# PulseOxi.net
KiCad netlist of a schematic drawn in EAGLE
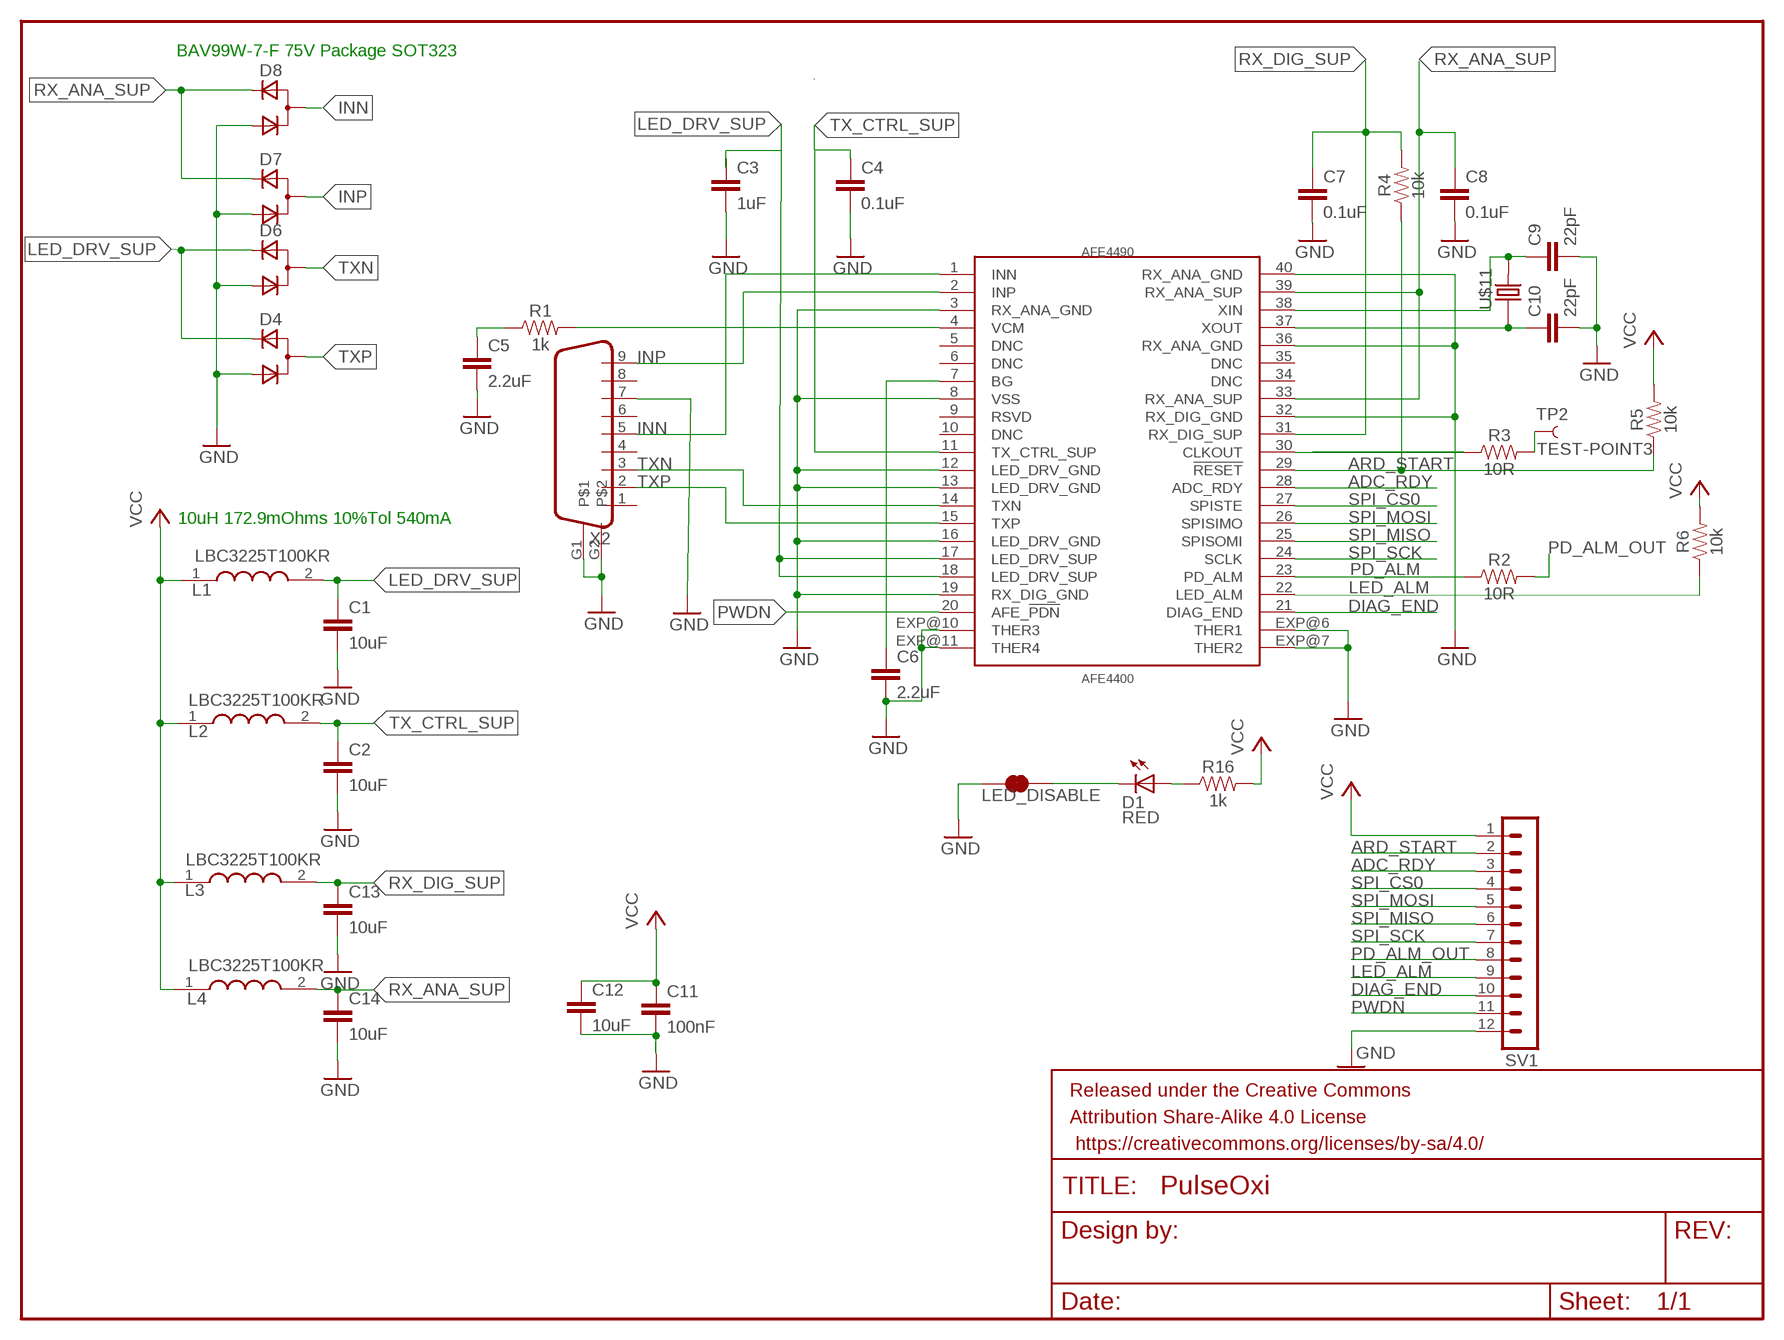
[diagram p0: schematic, sheet 1]

(export (version "E")
  (design (tool "Eeschema 10.0.6"))
  (components
    (comp (ref "AFE4490")
      (value "AFE4400")
      (footprint "eagle-import:QFN-40")
      (libsource (lib "eagle-import") (part "AFE4400"))
    )
    (comp (ref "C1")
      (value "10uF")
      (footprint "eagle-import:0603")
      (libsource (lib "eagle-import") (part "27PF-0603-50V-5%"))
    )
    (comp (ref "C2")
      (value "10uF")
      (footprint "eagle-import:0603")
      (libsource (lib "eagle-import") (part "27PF-0603-50V-5%"))
    )
    (comp (ref "C3")
      (value "1uF")
      (footprint "eagle-import:0603")
      (libsource (lib "eagle-import") (part "27PF-0603-50V-5%"))
    )
    (comp (ref "C4")
      (value "0.1uF")
      (footprint "eagle-import:0603")
      (libsource (lib "eagle-import") (part "27PF-0603-50V-5%"))
    )
    (comp (ref "C5")
      (value "2.2uF")
      (footprint "eagle-import:0603")
      (libsource (lib "eagle-import") (part "27PF-0603-50V-5%"))
    )
    (comp (ref "C6")
      (value "2.2uF")
      (footprint "eagle-import:0603")
      (libsource (lib "eagle-import") (part "27PF-0603-50V-5%"))
    )
    (comp (ref "C7")
      (value "0.1uF")
      (footprint "eagle-import:0603")
      (libsource (lib "eagle-import") (part "27PF-0603-50V-5%"))
    )
    (comp (ref "C8")
      (value "0.1uF")
      (footprint "eagle-import:0603")
      (libsource (lib "eagle-import") (part "27PF-0603-50V-5%"))
    )
    (comp (ref "C9")
      (value "22pF")
      (footprint "eagle-import:0603")
      (libsource (lib "eagle-import") (part "27PF-0603-50V-5%"))
    )
    (comp (ref "C10")
      (value "22pF")
      (footprint "eagle-import:0603")
      (libsource (lib "eagle-import") (part "27PF-0603-50V-5%"))
    )
    (comp (ref "C11")
      (value "100nF")
      (footprint "eagle-import:0603")
      (libsource (lib "eagle-import") (part "27PF-0603-50V-5%"))
    )
    (comp (ref "C12")
      (value "10uF")
      (footprint "eagle-import:0603")
      (libsource (lib "eagle-import") (part "27PF-0603-50V-5%"))
    )
    (comp (ref "C13")
      (value "10uF")
      (footprint "eagle-import:0603")
      (libsource (lib "eagle-import") (part "27PF-0603-50V-5%"))
    )
    (comp (ref "C14")
      (value "10uF")
      (footprint "eagle-import:0603")
      (libsource (lib "eagle-import") (part "27PF-0603-50V-5%"))
    )
    (comp (ref "D1")
      (value "RED")
      (footprint "eagle-import:LED-0603")
      (libsource (lib "eagle-import") (part "LED-RED0603"))
    )
    (comp (ref "D4")
      (value "D_ACACSOT323")
      (footprint "eagle-import:SOT323")
      (libsource (lib "eagle-import") (part "D_ACACSOT323"))
    )
    (comp (ref "D6")
      (value "D_ACACSOT323")
      (footprint "eagle-import:SOT323")
      (libsource (lib "eagle-import") (part "D_ACACSOT323"))
    )
    (comp (ref "D7")
      (value "D_ACACSOT323")
      (footprint "eagle-import:SOT323")
      (libsource (lib "eagle-import") (part "D_ACACSOT323"))
    )
    (comp (ref "D8")
      (value "D_ACACSOT323")
      (footprint "eagle-import:SOT323")
      (libsource (lib "eagle-import") (part "D_ACACSOT323"))
    )
    (comp (ref "FRAME1")
      (value "FRAME-LETTERNO_PACKAGE")
      (footprint "eagle-import:DUMMY")
      (fields (field (name "DESIGNER") "Nobody"))
      (libsource (lib "eagle-import") (part "FRAME-LETTERNO_PACKAGE"))
    )
    (comp (ref "L1")
      (value "LBC3225T100KR")
      (footprint "eagle-import:INDC3225X270N")
      (fields (field (name "MOUSER_PART_NUMBER") "963-LBC3225T100KR"))
      (libsource (lib "eagle-import") (part "LBC3225T100KR"))
    )
    (comp (ref "L2")
      (value "LBC3225T100KR")
      (footprint "eagle-import:INDC3225X270N")
      (fields (field (name "MOUSER_PART_NUMBER") "963-LBC3225T100KR"))
      (libsource (lib "eagle-import") (part "LBC3225T100KR"))
    )
    (comp (ref "L3")
      (value "LBC3225T100KR")
      (footprint "eagle-import:INDC3225X270N")
      (fields (field (name "MOUSER_PART_NUMBER") "963-LBC3225T100KR"))
      (libsource (lib "eagle-import") (part "LBC3225T100KR"))
    )
    (comp (ref "L4")
      (value "LBC3225T100KR")
      (footprint "eagle-import:INDC3225X270N")
      (fields (field (name "MOUSER_PART_NUMBER") "963-LBC3225T100KR"))
      (libsource (lib "eagle-import") (part "LBC3225T100KR"))
    )
    (comp (ref "LED_DISABLE")
      (value "JUMPER-SMT_2_NC_TRACE_SILK")
      (footprint "eagle-import:SMT-JUMPER_2_NC_TRACE_SILK")
      (libsource (lib "eagle-import") (part "JUMPER-SMT_2_NC_TRACE_SILK"))
    )
    (comp (ref "R1")
      (value "1k")
      (footprint "eagle-import:0603")
      (libsource (lib "eagle-import") (part "1KOHM-0603-1/10W-1%"))
    )
    (comp (ref "R2")
      (value "10R")
      (footprint "eagle-import:0603")
      (libsource (lib "eagle-import") (part "1.8MOHM"))
    )
    (comp (ref "R3")
      (value "10R")
      (footprint "eagle-import:0603")
      (libsource (lib "eagle-import") (part "1.8MOHM"))
    )
    (comp (ref "R4")
      (value "10k")
      (footprint "eagle-import:0603")
      (libsource (lib "eagle-import") (part "1.8MOHM"))
    )
    (comp (ref "R5")
      (value "10k")
      (footprint "eagle-import:0603")
      (libsource (lib "eagle-import") (part "1.8MOHM"))
    )
    (comp (ref "R6")
      (value "10k")
      (footprint "eagle-import:0603")
      (libsource (lib "eagle-import") (part "1.8MOHM"))
    )
    (comp (ref "R16")
      (value "1k")
      (footprint "eagle-import:0603")
      (libsource (lib "eagle-import") (part "1KOHM-0603-1/10W-1%"))
    )
    (comp (ref "SV1")
      (value "MA12-1")
      (footprint "eagle-import:MA12-1")
      (libsource (lib "eagle-import") (part "MA12-1"))
    )
    (comp (ref "TP2")
      (value "TEST-POINT3")
      (footprint "eagle-import:PAD.03X.03")
      (libsource (lib "eagle-import") (part "TEST-POINT3"))
    )
    (comp (ref "U$11")
      (value "ABM3")
      (footprint "eagle-import:ABM3")
      (libsource (lib "eagle-import") (part "ABM3"))
    )
    (comp (ref "X2")
      (value "DB9")
      (footprint "eagle-import:DB9")
      (libsource (lib "eagle-import") (part "DB9"))
    )
  )
  (nets
    (net (code "1") (name "/ADC_RDY") (class "Default")
      (node (ref "AFE4490") (pin "28") (pinfunction "ADC_RDY_28") (pintype "bidirectional"))
      (node (ref "SV1") (pin "3") (pinfunction "3_3") (pintype "passive"))
    )
    (net (code "2") (name "/ARD_START") (class "Default")
      (node (ref "AFE4490") (pin "29") (pinfunction "~{RESET}_29") (pintype "bidirectional"))
      (node (ref "R4") (pin "1") (pinfunction "1_1") (pintype "passive"))
      (node (ref "R5") (pin "1") (pinfunction "1_1") (pintype "passive"))
      (node (ref "SV1") (pin "2") (pinfunction "2_2") (pintype "passive"))
    )
    (net (code "3") (name "/DIAG_END") (class "Default")
      (node (ref "AFE4490") (pin "21") (pinfunction "DIAG_END_21") (pintype "bidirectional"))
      (node (ref "SV1") (pin "10") (pinfunction "10_10") (pintype "passive"))
    )
    (net (code "4") (name "/LED_ALM") (class "Default")
      (node (ref "AFE4490") (pin "22") (pinfunction "LED_ALM_22") (pintype "bidirectional"))
      (node (ref "R6") (pin "1") (pinfunction "1_1") (pintype "passive"))
      (node (ref "SV1") (pin "9") (pinfunction "9_9") (pintype "passive"))
    )
    (net (code "5") (name "/PD_ALM") (class "Default")
      (node (ref "AFE4490") (pin "23") (pinfunction "PD_ALM_23") (pintype "bidirectional"))
      (node (ref "R2") (pin "1") (pinfunction "1_1") (pintype "passive"))
    )
    (net (code "6") (name "/PD_ALM_OUT") (class "Default")
      (node (ref "R2") (pin "2") (pinfunction "2_2") (pintype "passive"))
      (node (ref "SV1") (pin "8") (pinfunction "8_8") (pintype "passive"))
    )
    (net (code "7") (name "/SPI_CS0") (class "Default")
      (node (ref "AFE4490") (pin "27") (pinfunction "SPISTE_27") (pintype "bidirectional"))
      (node (ref "SV1") (pin "4") (pinfunction "4_4") (pintype "passive"))
    )
    (net (code "8") (name "/SPI_MISO") (class "Default")
      (node (ref "AFE4490") (pin "25") (pinfunction "SPISOMI_25") (pintype "bidirectional"))
      (node (ref "SV1") (pin "6") (pinfunction "6_6") (pintype "passive"))
    )
    (net (code "9") (name "/SPI_MOSI") (class "Default")
      (node (ref "AFE4490") (pin "26") (pinfunction "SPISIMO_26") (pintype "bidirectional"))
      (node (ref "SV1") (pin "5") (pinfunction "5_5") (pintype "passive"))
    )
    (net (code "10") (name "/SPI_SCK") (class "Default")
      (node (ref "AFE4490") (pin "24") (pinfunction "SCLK_24") (pintype "bidirectional"))
      (node (ref "SV1") (pin "7") (pinfunction "7_7") (pintype "passive"))
    )
    (net (code "11") (name "GND") (class "Default")
      (node (ref "AFE4490") (pin "12") (pinfunction "LED_DRV_GND_12") (pintype "bidirectional"))
      (node (ref "AFE4490") (pin "13") (pinfunction "LED_DRV_GND_13") (pintype "bidirectional"))
      (node (ref "AFE4490") (pin "16") (pinfunction "LED_DRV_GND_16") (pintype "bidirectional"))
      (node (ref "AFE4490") (pin "19") (pinfunction "RX_DIG_GND_19") (pintype "bidirectional"))
      (node (ref "AFE4490") (pin "3") (pinfunction "RX_ANA_GND_3") (pintype "bidirectional"))
      (node (ref "AFE4490") (pin "32") (pinfunction "RX_DIG_GND_32") (pintype "bidirectional"))
      (node (ref "AFE4490") (pin "36") (pinfunction "RX_ANA_GND_36") (pintype "bidirectional"))
      (node (ref "AFE4490") (pin "40") (pinfunction "RX_ANA_GND_40") (pintype "bidirectional"))
      (node (ref "AFE4490") (pin "8") (pinfunction "VSS_8") (pintype "bidirectional"))
      (node (ref "AFE4490") (pin "EXP@10") (pinfunction "THER3_EXP@10") (pintype "bidirectional"))
      (node (ref "AFE4490") (pin "EXP@11") (pinfunction "THER4_EXP@11") (pintype "bidirectional"))
      (node (ref "AFE4490") (pin "EXP@6") (pinfunction "THER1_EXP@6") (pintype "bidirectional"))
      (node (ref "AFE4490") (pin "EXP@7") (pinfunction "THER2_EXP@7") (pintype "bidirectional"))
      (node (ref "C1") (pin "2") (pinfunction "2_2") (pintype "passive"))
      (node (ref "C10") (pin "2") (pinfunction "2_2") (pintype "passive"))
      (node (ref "C11") (pin "2") (pinfunction "2_2") (pintype "passive"))
      (node (ref "C12") (pin "2") (pinfunction "2_2") (pintype "passive"))
      (node (ref "C13") (pin "2") (pinfunction "2_2") (pintype "passive"))
      (node (ref "C14") (pin "2") (pinfunction "2_2") (pintype "passive"))
      (node (ref "C2") (pin "2") (pinfunction "2_2") (pintype "passive"))
      (node (ref "C3") (pin "2") (pinfunction "2_2") (pintype "passive"))
      (node (ref "C4") (pin "2") (pinfunction "2_2") (pintype "passive"))
      (node (ref "C5") (pin "2") (pinfunction "2_2") (pintype "passive"))
      (node (ref "C6") (pin "2") (pinfunction "2_2") (pintype "passive"))
      (node (ref "C7") (pin "2") (pinfunction "2_2") (pintype "passive"))
      (node (ref "C8") (pin "2") (pinfunction "2_2") (pintype "passive"))
      (node (ref "C9") (pin "2") (pinfunction "2_2") (pintype "passive"))
      (node (ref "D4") (pin "2") (pinfunction "C_2") (pintype "passive"))
      (node (ref "D6") (pin "2") (pinfunction "C_2") (pintype "passive"))
      (node (ref "D7") (pin "2") (pinfunction "C_2") (pintype "passive"))
      (node (ref "D8") (pin "2") (pinfunction "C_2") (pintype "passive"))
      (node (ref "LED_DISABLE") (pin "1") (pinfunction "1_1") (pintype "passive"))
      (node (ref "SV1") (pin "12") (pinfunction "12_12") (pintype "passive"))
      (node (ref "X2") (pin "7") (pinfunction "7_7") (pintype "passive"))
      (node (ref "X2") (pin "G1") (pinfunction "P$1_G1") (pintype "bidirectional"))
      (node (ref "X2") (pin "G2") (pinfunction "P$2_G2") (pintype "bidirectional"))
    )
    (net (code "12") (name "INN") (class "Default")
      (node (ref "AFE4490") (pin "1") (pinfunction "INN_1") (pintype "bidirectional"))
      (node (ref "D8") (pin "1") (pinfunction "CA_1") (pintype "passive"))
      (node (ref "X2") (pin "5") (pinfunction "5_5") (pintype "passive"))
    )
    (net (code "13") (name "INP") (class "Default")
      (node (ref "AFE4490") (pin "2") (pinfunction "INP_2") (pintype "bidirectional"))
      (node (ref "D7") (pin "1") (pinfunction "CA_1") (pintype "passive"))
      (node (ref "X2") (pin "9") (pinfunction "9_9") (pintype "passive"))
    )
    (net (code "14") (name "LED_DRV_SUP") (class "Default")
      (node (ref "AFE4490") (pin "17") (pinfunction "LED_DRV_SUP_17") (pintype "bidirectional"))
      (node (ref "AFE4490") (pin "18") (pinfunction "LED_DRV_SUP_18") (pintype "bidirectional"))
      (node (ref "C1") (pin "1") (pinfunction "1_1") (pintype "passive"))
      (node (ref "C3") (pin "1") (pinfunction "1_1") (pintype "passive"))
      (node (ref "D4") (pin "3") (pinfunction "A_3") (pintype "passive"))
      (node (ref "D6") (pin "3") (pinfunction "A_3") (pintype "passive"))
      (node (ref "L1") (pin "2") (pinfunction "2_2") (pintype "bidirectional"))
    )
    (net (code "15") (name "Net-(AFE4490-BG)") (class "Default")
      (node (ref "AFE4490") (pin "7") (pinfunction "BG_7") (pintype "bidirectional"))
      (node (ref "C6") (pin "1") (pinfunction "1_1") (pintype "passive"))
    )
    (net (code "16") (name "Net-(AFE4490-CLKOUT)") (class "Default")
      (node (ref "AFE4490") (pin "30") (pinfunction "CLKOUT_30") (pintype "bidirectional"))
      (node (ref "R3") (pin "1") (pinfunction "1_1") (pintype "passive"))
    )
    (net (code "17") (name "Net-(AFE4490-VCM)") (class "Default")
      (node (ref "AFE4490") (pin "4") (pinfunction "VCM_4") (pintype "bidirectional"))
      (node (ref "R1") (pin "2") (pinfunction "2_2") (pintype "passive"))
    )
    (net (code "18") (name "Net-(AFE4490-XIN)") (class "Default")
      (node (ref "AFE4490") (pin "38") (pinfunction "XIN_38") (pintype "bidirectional"))
      (node (ref "C9") (pin "1") (pinfunction "1_1") (pintype "passive"))
      (node (ref "U$11") (pin "2") (pinfunction "2_2") (pintype "passive"))
    )
    (net (code "19") (name "Net-(AFE4490-XOUT)") (class "Default")
      (node (ref "AFE4490") (pin "37") (pinfunction "XOUT_37") (pintype "bidirectional"))
      (node (ref "C10") (pin "1") (pinfunction "1_1") (pintype "passive"))
      (node (ref "U$11") (pin "1") (pinfunction "1_1") (pintype "passive"))
    )
    (net (code "20") (name "Net-(C5-Pad1)") (class "Default")
      (node (ref "C5") (pin "1") (pinfunction "1_1") (pintype "passive"))
      (node (ref "R1") (pin "1") (pinfunction "1_1") (pintype "passive"))
    )
    (net (code "21") (name "Net-(D1-PadA)") (class "Default")
      (node (ref "D1") (pin "A") (pinfunction "A_A") (pintype "passive"))
      (node (ref "R16") (pin "1") (pinfunction "1_1") (pintype "passive"))
    )
    (net (code "22") (name "Net-(D1-PadC)") (class "Default")
      (node (ref "D1") (pin "C") (pinfunction "C_C") (pintype "passive"))
      (node (ref "LED_DISABLE") (pin "2") (pinfunction "2_2") (pintype "passive"))
    )
    (net (code "23") (name "Net-(TP2-1)") (class "Default")
      (node (ref "R3") (pin "2") (pinfunction "2_2") (pintype "passive"))
      (node (ref "TP2") (pin "P$1") (pinfunction "1_P$1") (pintype "bidirectional"))
    )
    (net (code "24") (name "PWDN") (class "Default")
      (node (ref "AFE4490") (pin "20") (pinfunction "AFE_~{PDN}_20") (pintype "bidirectional"))
      (node (ref "SV1") (pin "11") (pinfunction "11_11") (pintype "passive"))
    )
    (net (code "25") (name "RX_ANA_SUP") (class "Default")
      (node (ref "AFE4490") (pin "33") (pinfunction "RX_ANA_SUP_33") (pintype "bidirectional"))
      (node (ref "AFE4490") (pin "39") (pinfunction "RX_ANA_SUP_39") (pintype "bidirectional"))
      (node (ref "C14") (pin "1") (pinfunction "1_1") (pintype "passive"))
      (node (ref "C8") (pin "1") (pinfunction "1_1") (pintype "passive"))
      (node (ref "D7") (pin "3") (pinfunction "A_3") (pintype "passive"))
      (node (ref "D8") (pin "3") (pinfunction "A_3") (pintype "passive"))
      (node (ref "L4") (pin "2") (pinfunction "2_2") (pintype "bidirectional"))
    )
    (net (code "26") (name "RX_DIG_SUP") (class "Default")
      (node (ref "AFE4490") (pin "31") (pinfunction "RX_DIG_SUP_31") (pintype "bidirectional"))
      (node (ref "C13") (pin "1") (pinfunction "1_1") (pintype "passive"))
      (node (ref "C7") (pin "1") (pinfunction "1_1") (pintype "passive"))
      (node (ref "L3") (pin "2") (pinfunction "2_2") (pintype "bidirectional"))
      (node (ref "R4") (pin "2") (pinfunction "2_2") (pintype "passive"))
    )
    (net (code "27") (name "TXN") (class "Default")
      (node (ref "AFE4490") (pin "14") (pinfunction "TXN_14") (pintype "bidirectional"))
      (node (ref "D6") (pin "1") (pinfunction "CA_1") (pintype "passive"))
      (node (ref "X2") (pin "3") (pinfunction "3_3") (pintype "passive"))
    )
    (net (code "28") (name "TXP") (class "Default")
      (node (ref "AFE4490") (pin "15") (pinfunction "TXP_15") (pintype "bidirectional"))
      (node (ref "D4") (pin "1") (pinfunction "CA_1") (pintype "passive"))
      (node (ref "X2") (pin "2") (pinfunction "2_2") (pintype "passive"))
    )
    (net (code "29") (name "TX_CTRL_SUP") (class "Default")
      (node (ref "AFE4490") (pin "11") (pinfunction "TX_CTRL_SUP_11") (pintype "bidirectional"))
      (node (ref "C2") (pin "1") (pinfunction "1_1") (pintype "passive"))
      (node (ref "C4") (pin "1") (pinfunction "1_1") (pintype "passive"))
      (node (ref "L2") (pin "2") (pinfunction "2_2") (pintype "bidirectional"))
    )
    (net (code "30") (name "VCC") (class "Default")
      (node (ref "C11") (pin "1") (pinfunction "1_1") (pintype "passive"))
      (node (ref "C12") (pin "1") (pinfunction "1_1") (pintype "passive"))
      (node (ref "L1") (pin "1") (pinfunction "1_1") (pintype "bidirectional"))
      (node (ref "L2") (pin "1") (pinfunction "1_1") (pintype "bidirectional"))
      (node (ref "L3") (pin "1") (pinfunction "1_1") (pintype "bidirectional"))
      (node (ref "L4") (pin "1") (pinfunction "1_1") (pintype "bidirectional"))
      (node (ref "R16") (pin "2") (pinfunction "2_2") (pintype "passive"))
      (node (ref "R5") (pin "2") (pinfunction "2_2") (pintype "passive"))
      (node (ref "R6") (pin "2") (pinfunction "2_2") (pintype "passive"))
      (node (ref "SV1") (pin "1") (pinfunction "1_1") (pintype "passive"))
    )
    (net (code "31") (name "unconnected-(AFE4490-DNC-Pad5)") (class "Default")
      (node (ref "AFE4490") (pin "5") (pinfunction "DNC_5") (pintype "bidirectional"))
    )
    (net (code "32") (name "unconnected-(AFE4490-DNC-Pad6)") (class "Default")
      (node (ref "AFE4490") (pin "6") (pinfunction "DNC_6") (pintype "bidirectional"))
    )
    (net (code "33") (name "unconnected-(AFE4490-DNC-Pad10)") (class "Default")
      (node (ref "AFE4490") (pin "10") (pinfunction "DNC_10") (pintype "bidirectional"))
    )
    (net (code "34") (name "unconnected-(AFE4490-DNC-Pad34)") (class "Default")
      (node (ref "AFE4490") (pin "34") (pinfunction "DNC_34") (pintype "bidirectional"))
    )
    (net (code "35") (name "unconnected-(AFE4490-DNC-Pad35)") (class "Default")
      (node (ref "AFE4490") (pin "35") (pinfunction "DNC_35") (pintype "bidirectional"))
    )
    (net (code "36") (name "unconnected-(AFE4490-RSVD-Pad9)") (class "Default")
      (node (ref "AFE4490") (pin "9") (pinfunction "RSVD_9") (pintype "bidirectional"))
    )
    (net (code "37") (name "unconnected-(X2-Pad1)") (class "Default")
      (node (ref "X2") (pin "1") (pinfunction "1_1") (pintype "passive"))
    )
    (net (code "38") (name "unconnected-(X2-Pad4)") (class "Default")
      (node (ref "X2") (pin "4") (pinfunction "4_4") (pintype "passive"))
    )
    (net (code "39") (name "unconnected-(X2-Pad6)") (class "Default")
      (node (ref "X2") (pin "6") (pinfunction "6_6") (pintype "passive"))
    )
    (net (code "40") (name "unconnected-(X2-Pad8)") (class "Default")
      (node (ref "X2") (pin "8") (pinfunction "8_8") (pintype "passive"))
    )
  )
)
